# vRef_Therm_Mod_v2.net
KiCad netlist of a schematic drawn in EAGLE
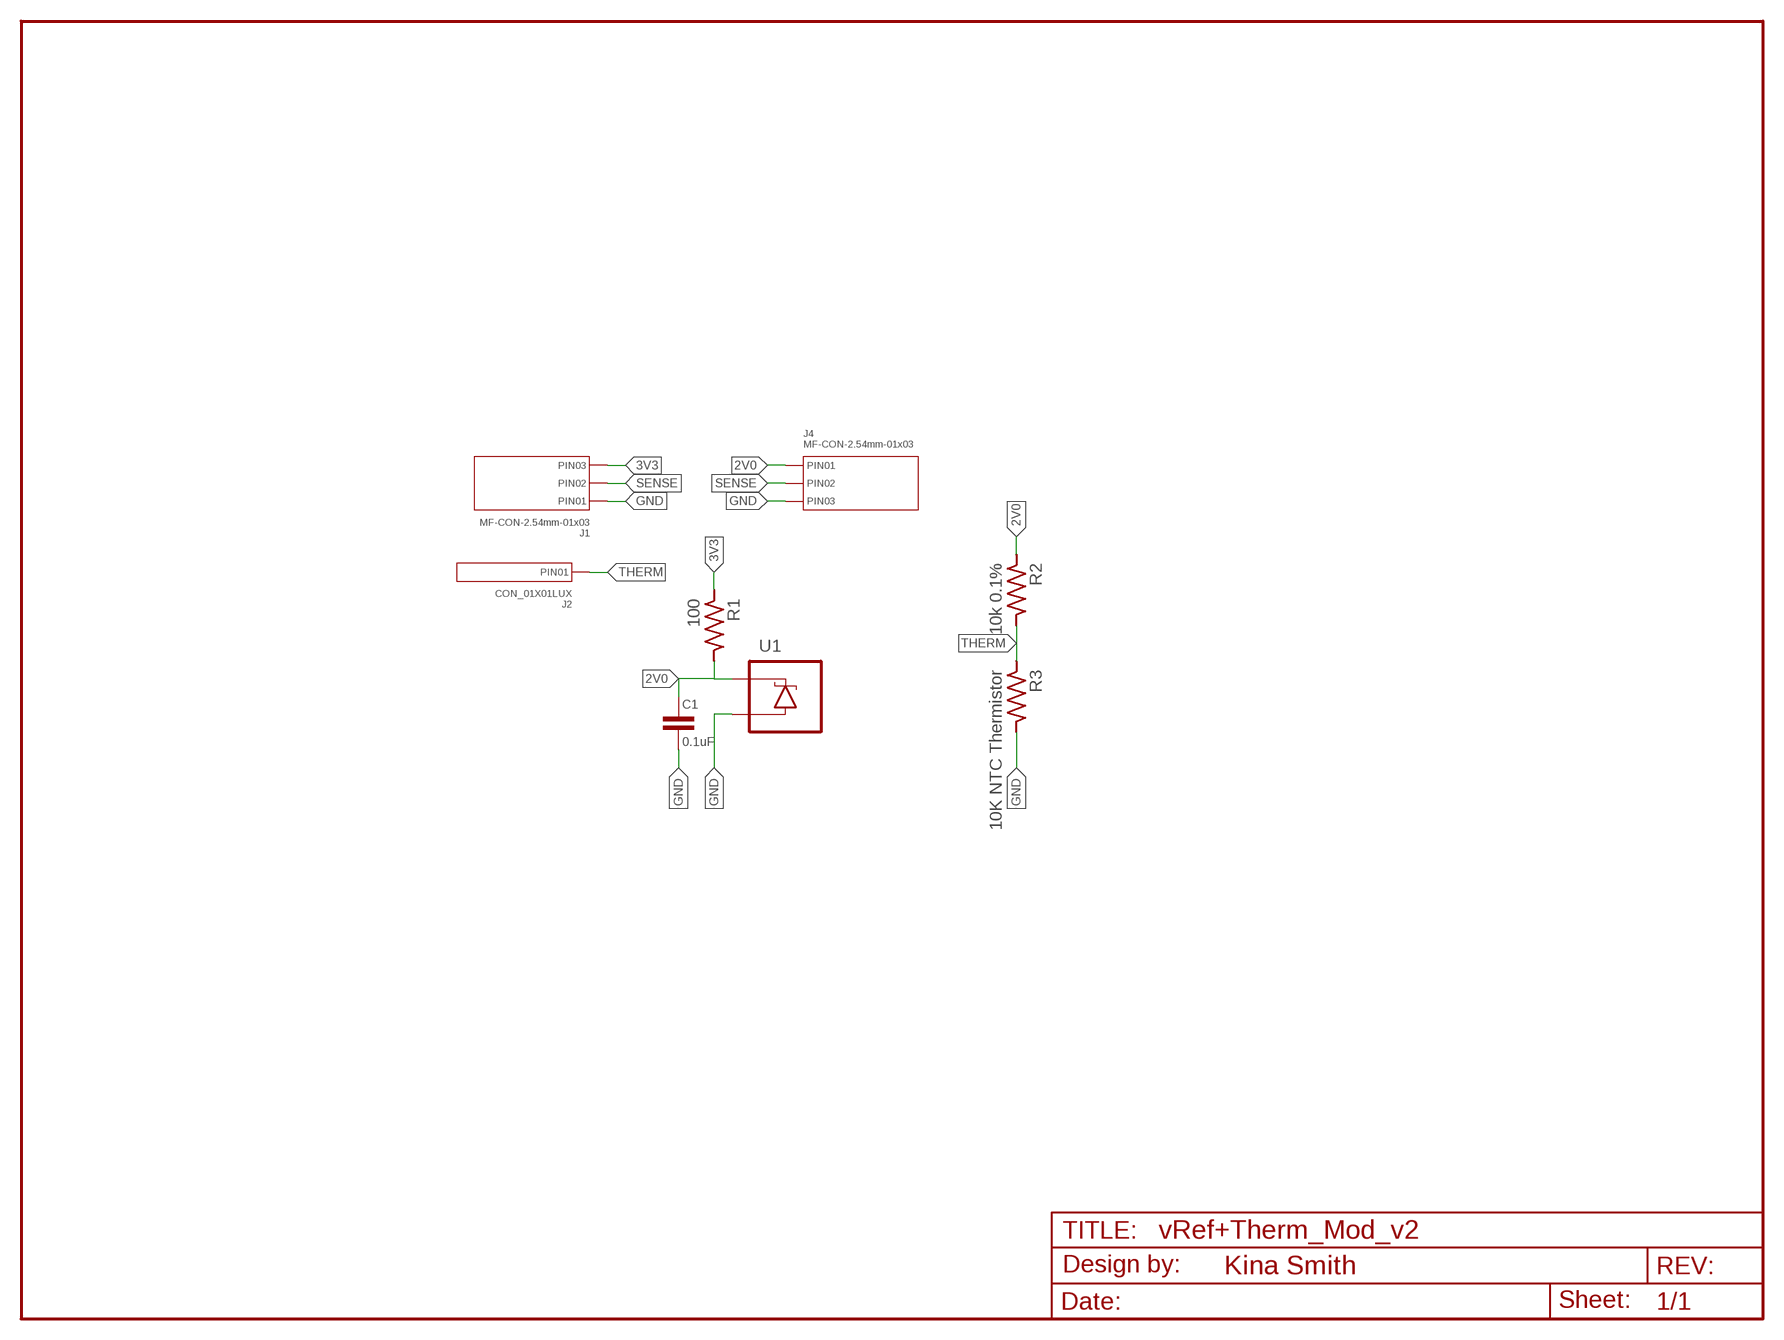
[diagram p0: schematic, sheet 1]

(export (version "E")
  (design (tool "Eeschema 10.0.6"))
  (components
    (comp (ref "C1")
      (value "0.1uF")
      (footprint "eagle-import:C0603-N")
      (libsource (lib "eagle-import") (part "CAPACITOR_NP0603-N"))
    )
    (comp (ref "FRAME1")
      (value "FRAME-LETTERNO_PACKAGE")
      (footprint "eagle-import:DUMMY")
      (fields (field (name "PARTNO") "NA") (field (name "DESIGNER") "Nobody"))
      (libsource (lib "eagle-import") (part "FRAME-LETTERNO_PACKAGE"))
    )
    (comp (ref "J1")
      (value "MF-CON-2.54mm-01x03")
      (footprint "eagle-import:PTH_2.54MM_01X03")
      (fields (field (name "HOUSEPART") "YES"))
      (libsource (lib "eagle-import") (part "CON_01X03_PTH_2.54MM"))
    )
    (comp (ref "J2")
      (value "CON_01X01LUX")
      (footprint "eagle-import:1X01_LUXEON-PAD")
      (libsource (lib "eagle-import") (part "CON_01X01LUX"))
    )
    (comp (ref "J4")
      (value "MF-CON-2.54mm-01x03")
      (footprint "eagle-import:PTH_2.54MM_01X03")
      (fields (field (name "HOUSEPART") "YES"))
      (libsource (lib "eagle-import") (part "CON_01X03_PTH_2.54MM"))
    )
    (comp (ref "R1")
      (value "100")
      (footprint "eagle-import:R0603-N")
      (libsource (lib "eagle-import") (part "RESISTOR0603-N"))
    )
    (comp (ref "R2")
      (value "10k 0.1%")
      (footprint "eagle-import:R0603-N")
      (libsource (lib "eagle-import") (part "RESISTOR0603-N"))
    )
    (comp (ref "R3")
      (value "10K NTC Thermistor")
      (footprint "eagle-import:R0603-N")
      (libsource (lib "eagle-import") (part "RESISTOR0603-N"))
    )
    (comp (ref "U1")
      (value "LM4040-SOT-23-3")
      (footprint "eagle-import:SOT23-3")
      (fields (field (name "PARTNO") "LM4040AIM3-2.0/NOPB "))
      (libsource (lib "eagle-import") (part "LM4040-SOT-23-3"))
    )
  )
  (nets
    (net (code "1") (name "2V0") (class "Default")
      (node (ref "C1") (pin "1") (pinfunction "1_1") (pintype "passive"))
      (node (ref "J4") (pin "P$1") (pinfunction "PIN1_P$1") (pintype "bidirectional"))
      (node (ref "R1") (pin "2") (pinfunction "P$2_2") (pintype "passive"))
      (node (ref "R2") (pin "1") (pinfunction "P$1_1") (pintype "passive"))
      (node (ref "U1") (pin "1") (pinfunction "C_1") (pintype "bidirectional"))
    )
    (net (code "2") (name "3V3") (class "Default")
      (node (ref "J1") (pin "P$3") (pinfunction "PIN3_P$3") (pintype "bidirectional"))
      (node (ref "R1") (pin "1") (pinfunction "P$1_1") (pintype "passive"))
    )
    (net (code "3") (name "GND") (class "Default")
      (node (ref "C1") (pin "2") (pinfunction "2_2") (pintype "passive"))
      (node (ref "J1") (pin "P$1") (pinfunction "PIN1_P$1") (pintype "bidirectional"))
      (node (ref "J4") (pin "P$3") (pinfunction "PIN3_P$3") (pintype "bidirectional"))
      (node (ref "R3") (pin "2") (pinfunction "P$2_2") (pintype "passive"))
      (node (ref "U1") (pin "2") (pinfunction "A_2") (pintype "bidirectional"))
    )
    (net (code "4") (name "SENSE") (class "Default")
      (node (ref "J1") (pin "P$2") (pinfunction "PIN2_P$2") (pintype "bidirectional"))
      (node (ref "J4") (pin "P$2") (pinfunction "PIN2_P$2") (pintype "bidirectional"))
    )
    (net (code "5") (name "THERM") (class "Default")
      (node (ref "J2") (pin "P$1") (pinfunction "PIN1_P$1") (pintype "bidirectional"))
      (node (ref "R2") (pin "2") (pinfunction "P$2_2") (pintype "passive"))
      (node (ref "R3") (pin "1") (pinfunction "P$1_1") (pintype "passive"))
    )
  )
)
